# Riego_Auto.net
KiCad netlist of a schematic drawn in EAGLE
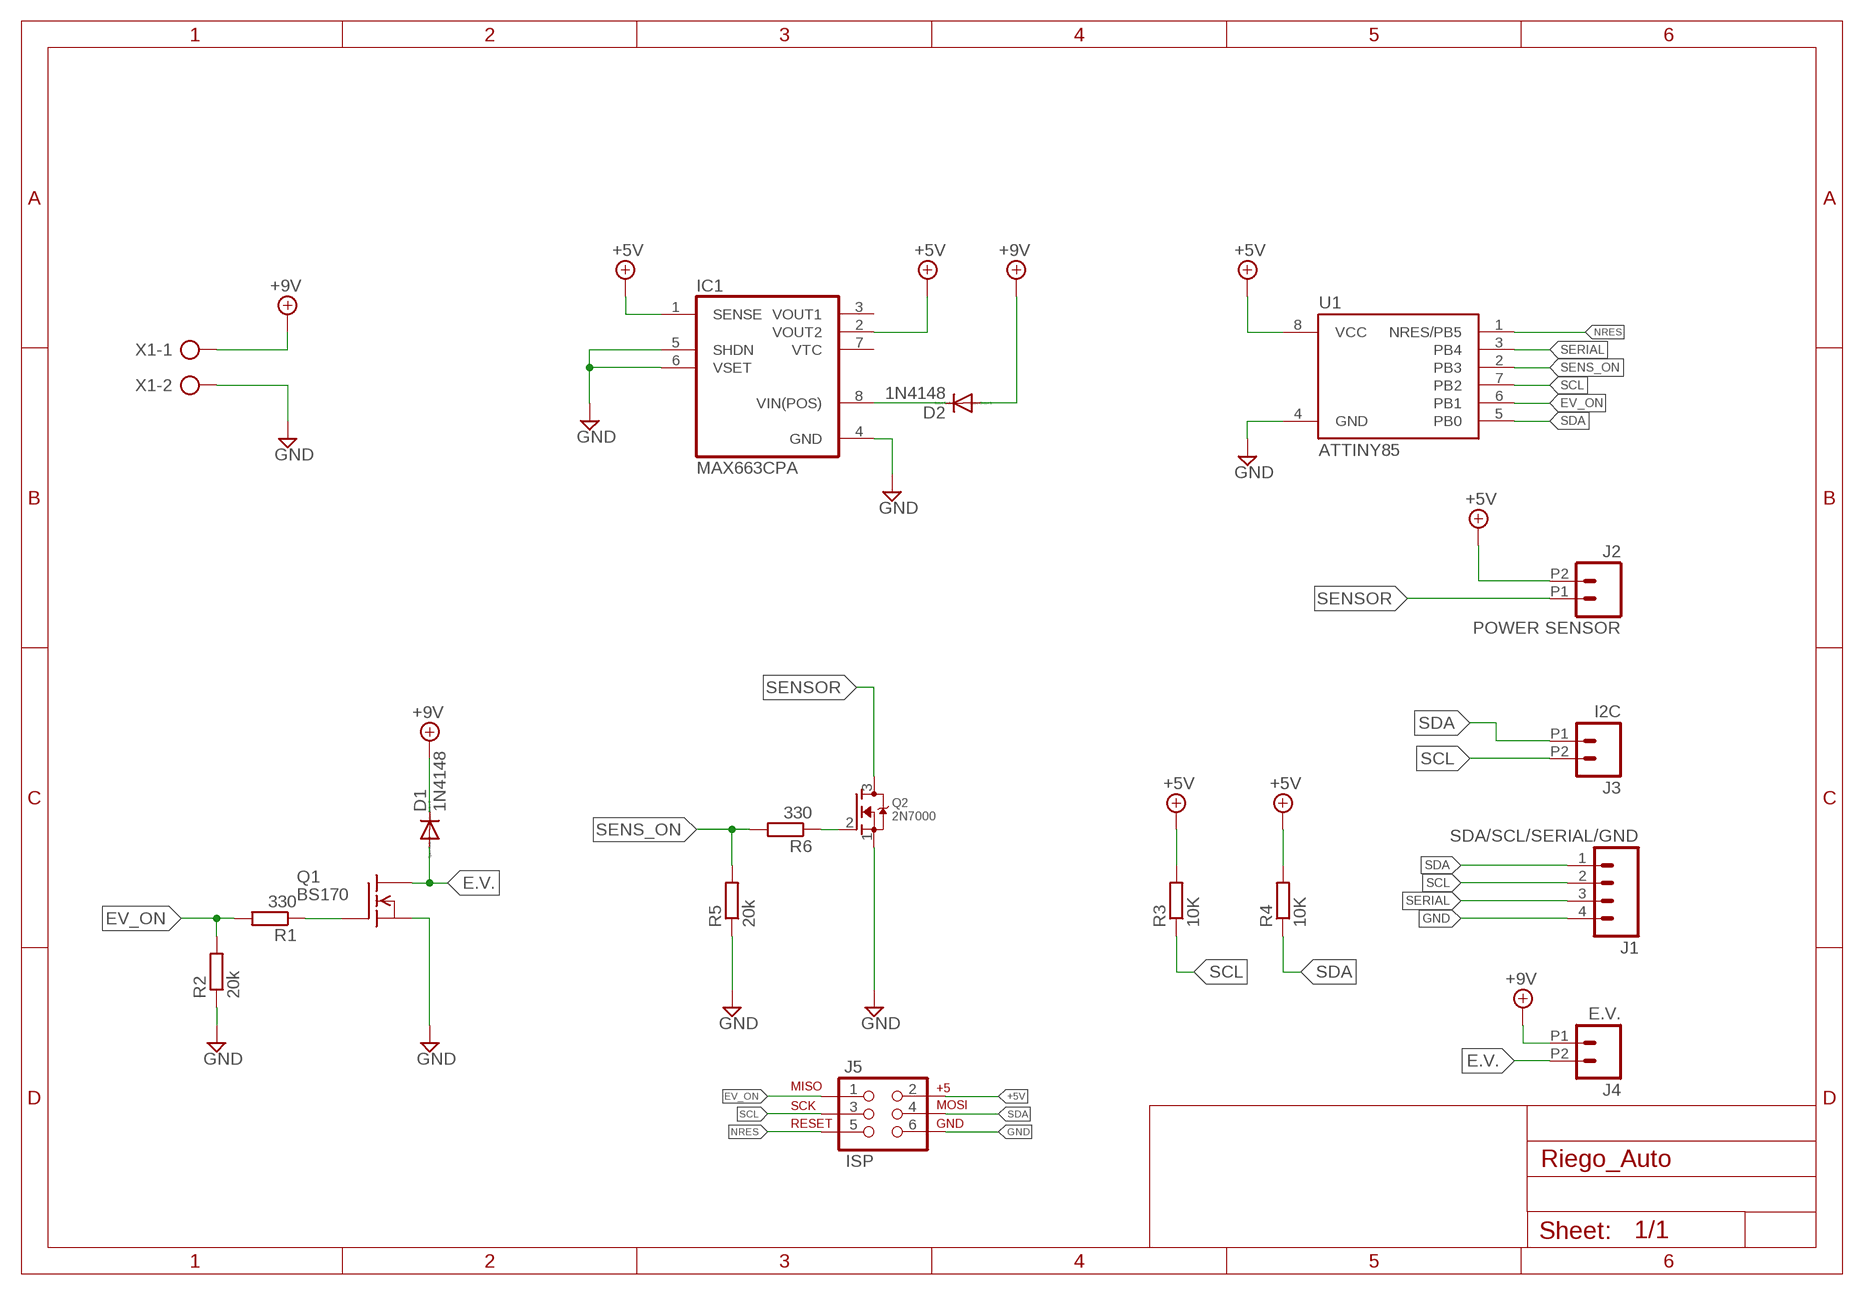
[diagram p0: schematic, sheet 1]

(export (version "E")
  (design (tool "Eeschema 10.0.6"))
  (components
    (comp (ref "D1")
      (value "1N4148")
      (footprint "eagle-import:DO35-7")
      (libsource (lib "eagle-import") (part "1N4148DO35-7"))
    )
    (comp (ref "D2")
      (value "1N4148")
      (footprint "eagle-import:DO35-7")
      (libsource (lib "eagle-import") (part "1N4148DO35-7"))
    )
    (comp (ref "IC1")
      (value "MAX663CPA")
      (footprint "eagle-import:DIL08")
      (fields (field (name "MPN") "MAX663CPA+"))
      (libsource (lib "eagle-import") (part "MAX663CPA"))
    )
    (comp (ref "J1")
      (value "SDA/SCL/SERIAL/GND")
      (footprint "eagle-import:1X04")
      (libsource (lib "eagle-import") (part "M04PTH"))
    )
    (comp (ref "J2")
      (value "POWER SENSOR")
      (footprint "eagle-import:1X02_2.54_SCREWTERM")
      (libsource (lib "eagle-import") (part "M022.54MM_SCREWTERM"))
    )
    (comp (ref "J3")
      (value "I2C")
      (footprint "eagle-import:1X02_2.54_SCREWTERM")
      (libsource (lib "eagle-import") (part "M022.54MM_SCREWTERM"))
    )
    (comp (ref "J4")
      (value "E.V.")
      (footprint "eagle-import:1X02_2.54_SCREWTERM")
      (libsource (lib "eagle-import") (part "M022.54MM_SCREWTERM"))
    )
    (comp (ref "J5")
      (value "ISP")
      (footprint "eagle-import:2X3")
      (libsource (lib "eagle-import") (part "AVR_SPI_PRG_6PTH"))
    )
    (comp (ref "Q1")
      (value "BS170")
      (footprint "eagle-import:TO92-INLINE")
      (libsource (lib "eagle-import") (part "FQN1N50CI"))
    )
    (comp (ref "Q2")
      (value "2N7000")
      (footprint "eagle-import:TO92-INLINE")
      (libsource (lib "eagle-import") (part "MOSFET-N"))
    )
    (comp (ref "R1")
      (value "330")
      (footprint "eagle-import:0204_7")
      (libsource (lib "eagle-import") (part "R-EU_0204/7"))
    )
    (comp (ref "R2")
      (value "20k")
      (footprint "eagle-import:0204_7")
      (libsource (lib "eagle-import") (part "R-EU_0204/7"))
    )
    (comp (ref "R3")
      (value "10K")
      (footprint "eagle-import:0204_7")
      (libsource (lib "eagle-import") (part "R-EU_0204/7"))
    )
    (comp (ref "R4")
      (value "10K")
      (footprint "eagle-import:0204_7")
      (libsource (lib "eagle-import") (part "R-EU_0204/7"))
    )
    (comp (ref "R5")
      (value "20k")
      (footprint "eagle-import:0204_7")
      (libsource (lib "eagle-import") (part "R-EU_0204/7"))
    )
    (comp (ref "R6")
      (value "330")
      (footprint "eagle-import:0204_7")
      (libsource (lib "eagle-import") (part "R-EU_0204/7"))
    )
    (comp (ref "U1")
      (value "ATTINY85")
      (footprint "eagle-import:DIL08")
      (libsource (lib "eagle-import") (part "ATTINY85DIL"))
    )
    (comp (ref "X1")
      (value "AK500/2")
      (footprint "eagle-import:AK500_2")
      (libsource (lib "eagle-import") (part "AK500/2"))
    )
  )
  (nets
    (net (code "1") (name "+5V") (class "Default")
      (node (ref "IC1") (pin "1") (pinfunction "SENSE_1") (pintype "input"))
      (node (ref "IC1") (pin "2") (pinfunction "VOUT2_2") (pintype "output"))
      (node (ref "J2") (pin "P2") (pinfunction "2_P2") (pintype "passive"))
      (node (ref "J5") (pin "2") (pinfunction "2_2") (pintype "passive"))
      (node (ref "R3") (pin "2") (pinfunction "2_2") (pintype "passive"))
      (node (ref "R4") (pin "2") (pinfunction "2_2") (pintype "passive"))
      (node (ref "U1") (pin "8") (pinfunction "VCC_8") (pintype "power_in"))
    )
    (net (code "2") (name "+9V") (class "Default")
      (node (ref "D1") (pin "C") (pinfunction "C_C") (pintype "passive"))
      (node (ref "D2") (pin "A") (pinfunction "A_A") (pintype "passive"))
      (node (ref "J4") (pin "P1") (pinfunction "1_P1") (pintype "passive"))
      (node (ref "X1") (pin "1") (pinfunction "KL_1") (pintype "passive"))
    )
    (net (code "3") (name "E.V.") (class "Default")
      (node (ref "D1") (pin "A") (pinfunction "A_A") (pintype "passive"))
      (node (ref "J4") (pin "P2") (pinfunction "2_P2") (pintype "passive"))
      (node (ref "Q1") (pin "1") (pinfunction "D_1") (pintype "passive"))
    )
    (net (code "4") (name "EV_ON") (class "Default")
      (node (ref "J5") (pin "1") (pinfunction "1_1") (pintype "passive"))
      (node (ref "R1") (pin "2") (pinfunction "2_2") (pintype "passive"))
      (node (ref "R2") (pin "2") (pinfunction "2_2") (pintype "passive"))
      (node (ref "U1") (pin "6") (pinfunction "PB1_6") (pintype "bidirectional"))
    )
    (net (code "5") (name "GND") (class "Default")
      (node (ref "IC1") (pin "4") (pinfunction "GND_4") (pintype "power_in"))
      (node (ref "IC1") (pin "5") (pinfunction "SHDN_5") (pintype "input"))
      (node (ref "IC1") (pin "6") (pinfunction "VSET_6") (pintype "input"))
      (node (ref "J1") (pin "4") (pinfunction "4_4") (pintype "passive"))
      (node (ref "J5") (pin "6") (pinfunction "6_6") (pintype "passive"))
      (node (ref "Q1") (pin "3") (pinfunction "S_3") (pintype "passive"))
      (node (ref "Q2") (pin "1") (pinfunction "S_1") (pintype "bidirectional"))
      (node (ref "R2") (pin "1") (pinfunction "1_1") (pintype "passive"))
      (node (ref "R5") (pin "1") (pinfunction "1_1") (pintype "passive"))
      (node (ref "U1") (pin "4") (pinfunction "GND_4") (pintype "power_in"))
      (node (ref "X1") (pin "2") (pinfunction "KL_2") (pintype "passive"))
    )
    (net (code "6") (name "NRES") (class "Default")
      (node (ref "J5") (pin "5") (pinfunction "5_5") (pintype "passive"))
      (node (ref "U1") (pin "1") (pinfunction "NRES/PB5_1") (pintype "bidirectional"))
    )
    (net (code "7") (name "Net-(IC1-VIN(POS))") (class "Default")
      (node (ref "D2") (pin "C") (pinfunction "C_C") (pintype "passive"))
      (node (ref "IC1") (pin "8") (pinfunction "VIN(POS)_8") (pintype "power_in"))
    )
    (net (code "8") (name "Net-(Q1-G)") (class "Default")
      (node (ref "Q1") (pin "2") (pinfunction "G_2") (pintype "passive"))
      (node (ref "R1") (pin "1") (pinfunction "1_1") (pintype "passive"))
    )
    (net (code "9") (name "Net-(Q2-G)") (class "Default")
      (node (ref "Q2") (pin "2") (pinfunction "G_2") (pintype "bidirectional"))
      (node (ref "R6") (pin "1") (pinfunction "1_1") (pintype "passive"))
    )
    (net (code "10") (name "SCL") (class "Default")
      (node (ref "J1") (pin "2") (pinfunction "2_2") (pintype "passive"))
      (node (ref "J3") (pin "P2") (pinfunction "2_P2") (pintype "passive"))
      (node (ref "J5") (pin "3") (pinfunction "3_3") (pintype "passive"))
      (node (ref "R3") (pin "1") (pinfunction "1_1") (pintype "passive"))
      (node (ref "U1") (pin "7") (pinfunction "PB2_7") (pintype "bidirectional"))
    )
    (net (code "11") (name "SDA") (class "Default")
      (node (ref "J1") (pin "1") (pinfunction "1_1") (pintype "passive"))
      (node (ref "J3") (pin "P1") (pinfunction "1_P1") (pintype "passive"))
      (node (ref "J5") (pin "4") (pinfunction "4_4") (pintype "passive"))
      (node (ref "R4") (pin "1") (pinfunction "1_1") (pintype "passive"))
      (node (ref "U1") (pin "5") (pinfunction "PB0_5") (pintype "bidirectional"))
    )
    (net (code "12") (name "SENSOR") (class "Default")
      (node (ref "J2") (pin "P1") (pinfunction "1_P1") (pintype "passive"))
      (node (ref "Q2") (pin "3") (pinfunction "D_3") (pintype "bidirectional"))
    )
    (net (code "13") (name "SENS_ON") (class "Default")
      (node (ref "R5") (pin "2") (pinfunction "2_2") (pintype "passive"))
      (node (ref "R6") (pin "2") (pinfunction "2_2") (pintype "passive"))
      (node (ref "U1") (pin "2") (pinfunction "PB3_2") (pintype "bidirectional"))
    )
    (net (code "14") (name "SERIAL") (class "Default")
      (node (ref "J1") (pin "3") (pinfunction "3_3") (pintype "passive"))
      (node (ref "U1") (pin "3") (pinfunction "PB4_3") (pintype "bidirectional"))
    )
    (net (code "15") (name "unconnected-(IC1-VOUT1-Pad3)") (class "Default")
      (node (ref "IC1") (pin "3") (pinfunction "VOUT1_3") (pintype "output"))
    )
    (net (code "16") (name "unconnected-(IC1-VTC-Pad7)") (class "Default")
      (node (ref "IC1") (pin "7") (pinfunction "VTC_7") (pintype "output"))
    )
  )
)
